# DEBUG_CONSOLE.net
KiCad netlist of a schematic drawn in Altium Designer
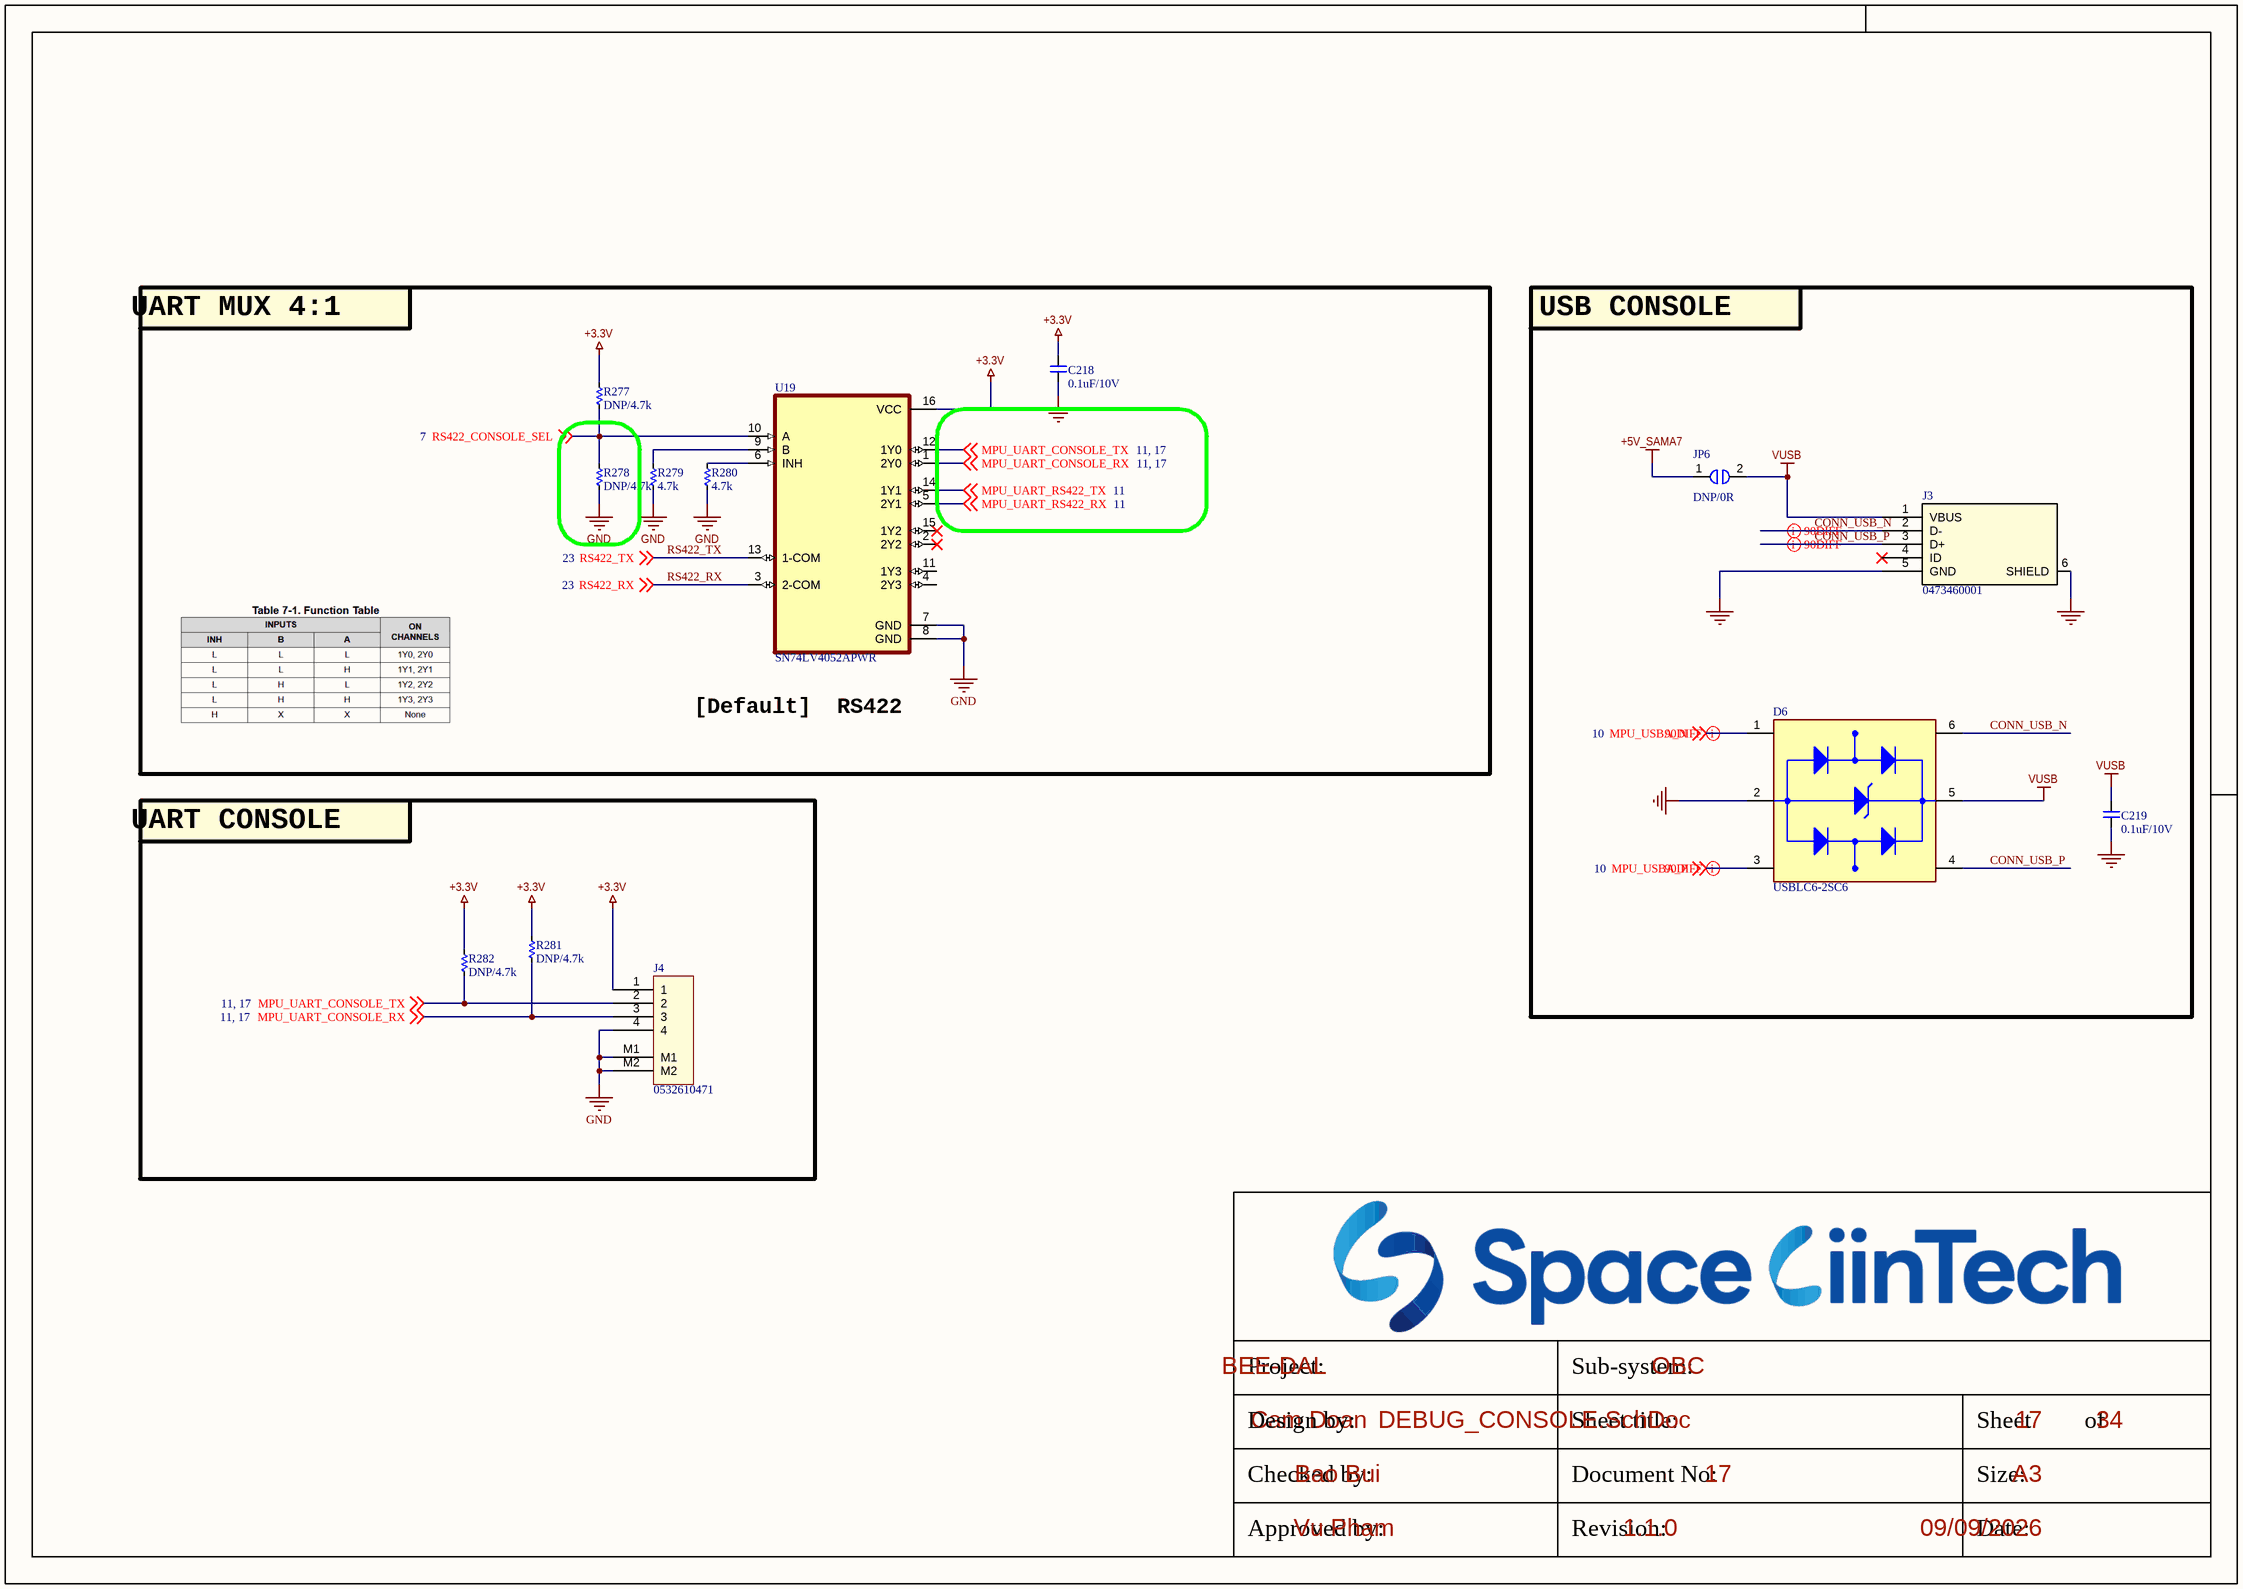
[diagram p0: DEBUG_CONSOLE.SchDoc]

(export (version "E")
  (design (tool "Eeschema 10.0.6"))
  (components
    (comp (ref "C218")
      (value "0.1uF/10V")
      (footprint "CAP_C_1005X50_L")
      (description "CAP")
      (libsource (lib "LABLIB") (part "_CAP_C_2"))
    )
    (comp (ref "C219")
      (value "0.1uF/10V")
      (footprint "CAP_C_1005X50_L")
      (description "CAP")
      (libsource (lib "LABLIB") (part "_CAP_C_2"))
    )
    (comp (ref "D6")
      (value "USBLC6-2SC6")
      (footprint "SOT95P280X145-6N")
      (description "17V Clamp 5A (8/20Âµs) Ipp Tvs Diode Surface Mount SOT-23-6")
      (fields (field (name "MF") "STMicroelectronics"))
      (libsource (lib "USBLC6-2SC6") (part "USBLC6-2SC6"))
    )
    (comp (ref "J3")
      (value "0473460001")
      (footprint "47346-0001_MOL")
      (description "No Description Available")
      (libsource (lib "obc_ver2") (part "USB_micro"))
    )
    (comp (ref "J4")
      (value "0532610471")
      (footprint "MOLEX_0532610471")
      (libsource (lib "IFBschelib") (part "Header 4x1_2M"))
    )
    (comp (ref "JP6")
      (value "DNP/0R")
      (footprint "RES_C_1608X60")
      (libsource (lib "LABLIB") (part "JUMPER_1_1"))
    )
    (comp (ref "R277")
      (value "DNP/4.7k")
      (footprint "RES_C_1005x30_L")
      (description "RES")
      (libsource (lib "IFBschelib") (part "_RES_B_2"))
    )
    (comp (ref "R278")
      (value "DNP/4.7k")
      (footprint "RES_C_1005x30_L")
      (description "RES")
      (libsource (lib "IFBschelib") (part "_RES_B_2"))
    )
    (comp (ref "R279")
      (value "4.7k")
      (footprint "RES_C_1005x30_L")
      (description "RES")
      (libsource (lib "IFBschelib") (part "_RES_B_2"))
    )
    (comp (ref "R280")
      (value "4.7k")
      (footprint "RES_C_1005x30_L")
      (description "RES")
      (libsource (lib "IFBschelib") (part "_RES_B_2"))
    )
    (comp (ref "R281")
      (value "DNP/4.7k")
      (footprint "RES_C_1005x30_L")
      (description "RES")
      (libsource (lib "IFBschelib") (part "_RES_B_2"))
    )
    (comp (ref "R282")
      (value "DNP/4.7k")
      (footprint "RES_C_1005x30_L")
      (description "RES")
      (libsource (lib "IFBschelib") (part "_RES_B_2"))
    )
    (comp (ref "U19")
      (value "SN74LV4052APWR")
      (footprint "SOP65P640X120-16N")
      (description "5-V, 4:1, 2-channel analog multiplexer")
      (fields (field (name "MF") "Texas Instruments"))
      (libsource (lib "IFBschelib") (part "SN74LV4052APWR"))
    )
  )
  (nets
    (net (code "1") (name "+3.3V") (class "Default")
      (node (ref "C218") (pin "2") (pinfunction "2_2") (pintype "passive"))
      (node (ref "J4") (pin "1") (pinfunction "1_1") (pintype "passive"))
      (node (ref "R277") (pin "1") (pinfunction "1_1") (pintype "passive"))
      (node (ref "R281") (pin "1") (pinfunction "1_1") (pintype "passive"))
      (node (ref "R282") (pin "1") (pinfunction "1_1") (pintype "passive"))
      (node (ref "U19") (pin "16") (pinfunction "VCC_16") (pintype "power_in"))
    )
    (net (code "2") (name "+5V_SAMA7") (class "Default")
      (node (ref "JP6") (pin "1") (pinfunction "1_1") (pintype "passive"))
    )
    (net (code "3") (name "/CONN_USB_N") (class "Default")
      (node (ref "D6") (pin "6") (pinfunction "I/O1_OUT_6") (pintype "passive"))
      (node (ref "J3") (pin "2") (pinfunction "D-_2") (pintype "passive"))
    )
    (net (code "4") (name "/CONN_USB_P") (class "Default")
      (node (ref "D6") (pin "4") (pinfunction "I/O2_OUT_4") (pintype "passive"))
      (node (ref "J3") (pin "3") (pinfunction "D+_3") (pintype "passive"))
    )
    (net (code "5") (name "GND") (class "Default")
      (node (ref "C218") (pin "1") (pinfunction "1_1") (pintype "passive"))
      (node (ref "C219") (pin "1") (pinfunction "1_1") (pintype "passive"))
      (node (ref "D6") (pin "2") (pinfunction "GND_2") (pintype "power_in"))
      (node (ref "J3") (pin "5") (pinfunction "GND_5") (pintype "power_in"))
      (node (ref "J3") (pin "6") (pinfunction "SHIELD_6") (pintype "passive"))
      (node (ref "J4") (pin "4") (pinfunction "4_4") (pintype "passive"))
      (node (ref "J4") (pin "M1") (pinfunction "M1_M1") (pintype "passive"))
      (node (ref "J4") (pin "M2") (pinfunction "M2_M2") (pintype "passive"))
      (node (ref "R278") (pin "2") (pinfunction "2_2") (pintype "passive"))
      (node (ref "R279") (pin "2") (pinfunction "2_2") (pintype "passive"))
      (node (ref "R280") (pin "2") (pinfunction "2_2") (pintype "passive"))
      (node (ref "U19") (pin "7") (pinfunction "GND_7") (pintype "power_in"))
      (node (ref "U19") (pin "8") (pinfunction "GND_8") (pintype "power_in"))
    )
    (net (code "6") (name "MPU_UART_CONSOLE_RX") (class "Default")
      (node (ref "J4") (pin "3") (pinfunction "3_3") (pintype "passive"))
      (node (ref "R281") (pin "2") (pinfunction "2_2") (pintype "passive"))
      (node (ref "U19") (pin "1") (pinfunction "2Y0_1") (pintype "bidirectional"))
    )
    (net (code "7") (name "MPU_UART_CONSOLE_TX") (class "Default")
      (node (ref "J4") (pin "2") (pinfunction "2_2") (pintype "passive"))
      (node (ref "R282") (pin "2") (pinfunction "2_2") (pintype "passive"))
      (node (ref "U19") (pin "12") (pinfunction "1Y0_12") (pintype "bidirectional"))
    )
    (net (code "8") (name "MPU_UART_RS422_RX") (class "Default")
      (node (ref "U19") (pin "5") (pinfunction "2Y1_5") (pintype "bidirectional"))
    )
    (net (code "9") (name "MPU_UART_RS422_TX") (class "Default")
      (node (ref "U19") (pin "14") (pinfunction "1Y1_14") (pintype "bidirectional"))
    )
    (net (code "10") (name "MPU_USBA_N") (class "Default")
      (node (ref "D6") (pin "1") (pinfunction "I/O1_IN_1") (pintype "passive"))
    )
    (net (code "11") (name "MPU_USBA_P") (class "Default")
      (node (ref "D6") (pin "3") (pinfunction "I/O2_IN_3") (pintype "passive"))
    )
    (net (code "12") (name "Net-(U19-B)") (class "Default")
      (node (ref "R279") (pin "1") (pinfunction "1_1") (pintype "passive"))
      (node (ref "U19") (pin "9") (pinfunction "B_9") (pintype "input"))
    )
    (net (code "13") (name "Net-(U19-INH)") (class "Default")
      (node (ref "R280") (pin "1") (pinfunction "1_1") (pintype "passive"))
      (node (ref "U19") (pin "6") (pinfunction "INH_6") (pintype "input"))
    )
    (net (code "14") (name "RS422_CONSOLE_SEL") (class "Default")
      (node (ref "R277") (pin "2") (pinfunction "2_2") (pintype "passive"))
      (node (ref "R278") (pin "1") (pinfunction "1_1") (pintype "passive"))
      (node (ref "U19") (pin "10") (pinfunction "A_10") (pintype "input"))
    )
    (net (code "15") (name "RS422_RX") (class "Default")
      (node (ref "U19") (pin "3") (pinfunction "2-COM_3") (pintype "bidirectional"))
    )
    (net (code "16") (name "RS422_TX") (class "Default")
      (node (ref "U19") (pin "13") (pinfunction "1-COM_13") (pintype "bidirectional"))
    )
    (net (code "17") (name "VUSB") (class "Default")
      (node (ref "C219") (pin "2") (pinfunction "2_2") (pintype "passive"))
      (node (ref "D6") (pin "5") (pinfunction "VBUS_5") (pintype "power_in"))
      (node (ref "J3") (pin "1") (pinfunction "VBUS_1") (pintype "passive"))
      (node (ref "JP6") (pin "2") (pinfunction "2_2") (pintype "passive"))
    )
    (net (code "18") (name "unconnected-(J3-ID-Pad4)") (class "Default")
      (node (ref "J3") (pin "4") (pinfunction "ID_4") (pintype "passive+no_connect"))
    )
    (net (code "19") (name "unconnected-(U19-1Y2-Pad15)") (class "Default")
      (node (ref "U19") (pin "15") (pinfunction "1Y2_15") (pintype "bidirectional+no_connect"))
    )
    (net (code "20") (name "unconnected-(U19-1Y3-Pad11)") (class "Default")
      (node (ref "U19") (pin "11") (pinfunction "1Y3_11") (pintype "bidirectional"))
    )
    (net (code "21") (name "unconnected-(U19-2Y2-Pad2)") (class "Default")
      (node (ref "U19") (pin "2") (pinfunction "2Y2_2") (pintype "bidirectional+no_connect"))
    )
    (net (code "22") (name "unconnected-(U19-2Y3-Pad4)") (class "Default")
      (node (ref "U19") (pin "4") (pinfunction "2Y3_4") (pintype "bidirectional"))
    )
  )
)
